# LVHV8ChanTranslation.net
KiCad netlist of a schematic drawn in Altium Designer
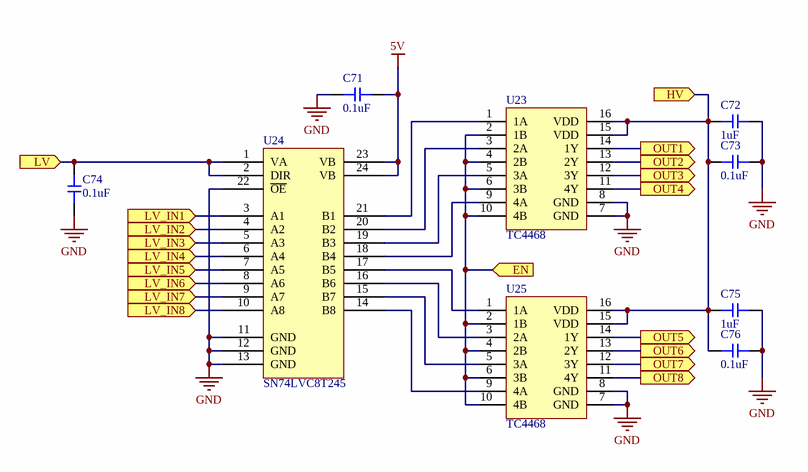
[diagram p0: LVHV8ChanTranslation.SchDoc]

(export (version "E")
  (design (tool "Eeschema 10.0.6"))
  (components
    (comp (ref "C71")
      (value "0.1uF")
      (footprint "0603-CAP")
      (description "Capacitor")
      (libsource (lib "AMDC") (part "Capacitor"))
    )
    (comp (ref "C72")
      (value "1uF")
      (footprint "0603-CAP")
      (description "Capacitor")
      (libsource (lib "AMDC") (part "Capacitor"))
    )
    (comp (ref "C73")
      (value "0.1uF")
      (footprint "0603-CAP")
      (description "Capacitor")
      (libsource (lib "AMDC") (part "Capacitor"))
    )
    (comp (ref "C74")
      (value "0.1uF")
      (footprint "0603-CAP")
      (description "Capacitor")
      (libsource (lib "AMDC") (part "Capacitor"))
    )
    (comp (ref "C75")
      (value "1uF")
      (footprint "0603-CAP")
      (description "Capacitor")
      (libsource (lib "AMDC") (part "Capacitor"))
    )
    (comp (ref "C76")
      (value "0.1uF")
      (footprint "0603-CAP")
      (description "Capacitor")
      (libsource (lib "AMDC") (part "Capacitor"))
    )
    (comp (ref "U23")
      (value "TC4468")
      (footprint "SOIC16_N - wide")
      (description "IC MOSFET DVR QUAD AND 16SOIC")
      (libsource (lib "AMDC") (part "TC4468"))
    )
    (comp (ref "U24")
      (value "SN74LVC8T245")
      (footprint "TSOP65P640X120-24N")
      (description "IC BUS TRANSCVR 8BIT 24TSSOP")
      (libsource (lib "AMDC") (part "SN74LVC8T245PWR"))
    )
    (comp (ref "U25")
      (value "TC4468")
      (footprint "SOIC16_N - wide")
      (description "IC MOSFET DVR QUAD AND 16SOIC")
      (libsource (lib "AMDC") (part "TC4468"))
    )
  )
  (nets
    (net (code "1") (name "/EN") (class "Default")
      (node (ref "U23") (pin "10") (pinfunction "4B_10") (pintype "passive"))
      (node (ref "U23") (pin "2") (pinfunction "1B_2") (pintype "passive"))
      (node (ref "U23") (pin "4") (pinfunction "2B_4") (pintype "passive"))
      (node (ref "U23") (pin "6") (pinfunction "3B_6") (pintype "passive"))
      (node (ref "U25") (pin "10") (pinfunction "4B_10") (pintype "passive"))
      (node (ref "U25") (pin "2") (pinfunction "1B_2") (pintype "passive"))
      (node (ref "U25") (pin "4") (pinfunction "2B_4") (pintype "passive"))
      (node (ref "U25") (pin "6") (pinfunction "3B_6") (pintype "passive"))
    )
    (net (code "2") (name "/HV") (class "Default")
      (node (ref "C72") (pin "1") (pinfunction "1_1") (pintype "passive"))
      (node (ref "C73") (pin "1") (pinfunction "1_1") (pintype "passive"))
      (node (ref "C75") (pin "1") (pinfunction "1_1") (pintype "passive"))
      (node (ref "C76") (pin "1") (pinfunction "1_1") (pintype "passive"))
      (node (ref "U23") (pin "15") (pinfunction "VDD_15") (pintype "passive"))
      (node (ref "U23") (pin "16") (pinfunction "VDD_16") (pintype "passive"))
      (node (ref "U25") (pin "15") (pinfunction "VDD_15") (pintype "passive"))
      (node (ref "U25") (pin "16") (pinfunction "VDD_16") (pintype "passive"))
    )
    (net (code "3") (name "/LV") (class "Default")
      (node (ref "C74") (pin "2") (pinfunction "2_2") (pintype "passive"))
      (node (ref "U24") (pin "1") (pinfunction "VA_1") (pintype "passive"))
      (node (ref "U24") (pin "2") (pinfunction "DIR_2") (pintype "passive"))
    )
    (net (code "4") (name "/LV_IN1") (class "Default")
      (node (ref "U24") (pin "3") (pinfunction "A1_3") (pintype "passive"))
    )
    (net (code "5") (name "/LV_IN2") (class "Default")
      (node (ref "U24") (pin "4") (pinfunction "A2_4") (pintype "passive"))
    )
    (net (code "6") (name "/LV_IN3") (class "Default")
      (node (ref "U24") (pin "5") (pinfunction "A3_5") (pintype "passive"))
    )
    (net (code "7") (name "/LV_IN4") (class "Default")
      (node (ref "U24") (pin "6") (pinfunction "A4_6") (pintype "passive"))
    )
    (net (code "8") (name "/LV_IN5") (class "Default")
      (node (ref "U24") (pin "7") (pinfunction "A5_7") (pintype "passive"))
    )
    (net (code "9") (name "/LV_IN6") (class "Default")
      (node (ref "U24") (pin "8") (pinfunction "A6_8") (pintype "passive"))
    )
    (net (code "10") (name "/LV_IN7") (class "Default")
      (node (ref "U24") (pin "9") (pinfunction "A7_9") (pintype "passive"))
    )
    (net (code "11") (name "/LV_IN8") (class "Default")
      (node (ref "U24") (pin "10") (pinfunction "A8_10") (pintype "passive"))
    )
    (net (code "12") (name "/OUT1") (class "Default")
      (node (ref "U23") (pin "14") (pinfunction "1Y_14") (pintype "passive"))
    )
    (net (code "13") (name "/OUT2") (class "Default")
      (node (ref "U23") (pin "13") (pinfunction "2Y_13") (pintype "passive"))
    )
    (net (code "14") (name "/OUT3") (class "Default")
      (node (ref "U23") (pin "12") (pinfunction "3Y_12") (pintype "passive"))
    )
    (net (code "15") (name "/OUT4") (class "Default")
      (node (ref "U23") (pin "11") (pinfunction "4Y_11") (pintype "passive"))
    )
    (net (code "16") (name "/OUT5") (class "Default")
      (node (ref "U25") (pin "14") (pinfunction "1Y_14") (pintype "passive"))
    )
    (net (code "17") (name "/OUT6") (class "Default")
      (node (ref "U25") (pin "13") (pinfunction "2Y_13") (pintype "passive"))
    )
    (net (code "18") (name "/OUT7") (class "Default")
      (node (ref "U25") (pin "12") (pinfunction "3Y_12") (pintype "passive"))
    )
    (net (code "19") (name "/OUT8") (class "Default")
      (node (ref "U25") (pin "11") (pinfunction "4Y_11") (pintype "passive"))
    )
    (net (code "20") (name "5V") (class "Default")
      (node (ref "C71") (pin "1") (pinfunction "1_1") (pintype "passive"))
      (node (ref "U24") (pin "23") (pinfunction "VB_23") (pintype "passive"))
      (node (ref "U24") (pin "24") (pinfunction "VB_24") (pintype "passive"))
    )
    (net (code "21") (name "GND") (class "Default")
      (node (ref "C71") (pin "2") (pinfunction "2_2") (pintype "passive"))
      (node (ref "C72") (pin "2") (pinfunction "2_2") (pintype "passive"))
      (node (ref "C73") (pin "2") (pinfunction "2_2") (pintype "passive"))
      (node (ref "C74") (pin "1") (pinfunction "1_1") (pintype "passive"))
      (node (ref "C75") (pin "2") (pinfunction "2_2") (pintype "passive"))
      (node (ref "C76") (pin "2") (pinfunction "2_2") (pintype "passive"))
      (node (ref "U23") (pin "7") (pinfunction "GND_7") (pintype "passive"))
      (node (ref "U23") (pin "8") (pinfunction "GND_8") (pintype "passive"))
      (node (ref "U24") (pin "11") (pinfunction "GND_11") (pintype "passive"))
      (node (ref "U24") (pin "12") (pinfunction "GND_12") (pintype "passive"))
      (node (ref "U24") (pin "13") (pinfunction "GND_13") (pintype "passive"))
      (node (ref "U24") (pin "22") (pinfunction "~{OE}_22") (pintype "passive"))
      (node (ref "U25") (pin "7") (pinfunction "GND_7") (pintype "passive"))
      (node (ref "U25") (pin "8") (pinfunction "GND_8") (pintype "passive"))
    )
    (net (code "22") (name "Net-(U23-1A)") (class "Default")
      (node (ref "U23") (pin "1") (pinfunction "1A_1") (pintype "passive"))
      (node (ref "U24") (pin "21") (pinfunction "B1_21") (pintype "passive"))
    )
    (net (code "23") (name "Net-(U23-2A)") (class "Default")
      (node (ref "U23") (pin "3") (pinfunction "2A_3") (pintype "passive"))
      (node (ref "U24") (pin "20") (pinfunction "B2_20") (pintype "passive"))
    )
    (net (code "24") (name "Net-(U23-3A)") (class "Default")
      (node (ref "U23") (pin "5") (pinfunction "3A_5") (pintype "passive"))
      (node (ref "U24") (pin "19") (pinfunction "B3_19") (pintype "passive"))
    )
    (net (code "25") (name "Net-(U23-4A)") (class "Default")
      (node (ref "U23") (pin "9") (pinfunction "4A_9") (pintype "passive"))
      (node (ref "U24") (pin "18") (pinfunction "B4_18") (pintype "passive"))
    )
    (net (code "26") (name "Net-(U24-B5)") (class "Default")
      (node (ref "U24") (pin "17") (pinfunction "B5_17") (pintype "passive"))
      (node (ref "U25") (pin "1") (pinfunction "1A_1") (pintype "passive"))
    )
    (net (code "27") (name "Net-(U24-B6)") (class "Default")
      (node (ref "U24") (pin "16") (pinfunction "B6_16") (pintype "passive"))
      (node (ref "U25") (pin "3") (pinfunction "2A_3") (pintype "passive"))
    )
    (net (code "28") (name "Net-(U24-B7)") (class "Default")
      (node (ref "U24") (pin "15") (pinfunction "B7_15") (pintype "passive"))
      (node (ref "U25") (pin "5") (pinfunction "3A_5") (pintype "passive"))
    )
    (net (code "29") (name "Net-(U24-B8)") (class "Default")
      (node (ref "U24") (pin "14") (pinfunction "B8_14") (pintype "passive"))
      (node (ref "U25") (pin "9") (pinfunction "4A_9") (pintype "passive"))
    )
  )
)
